# HoverBoard_CoolAndFun.net
KiCad netlist of a schematic drawn in EAGLE
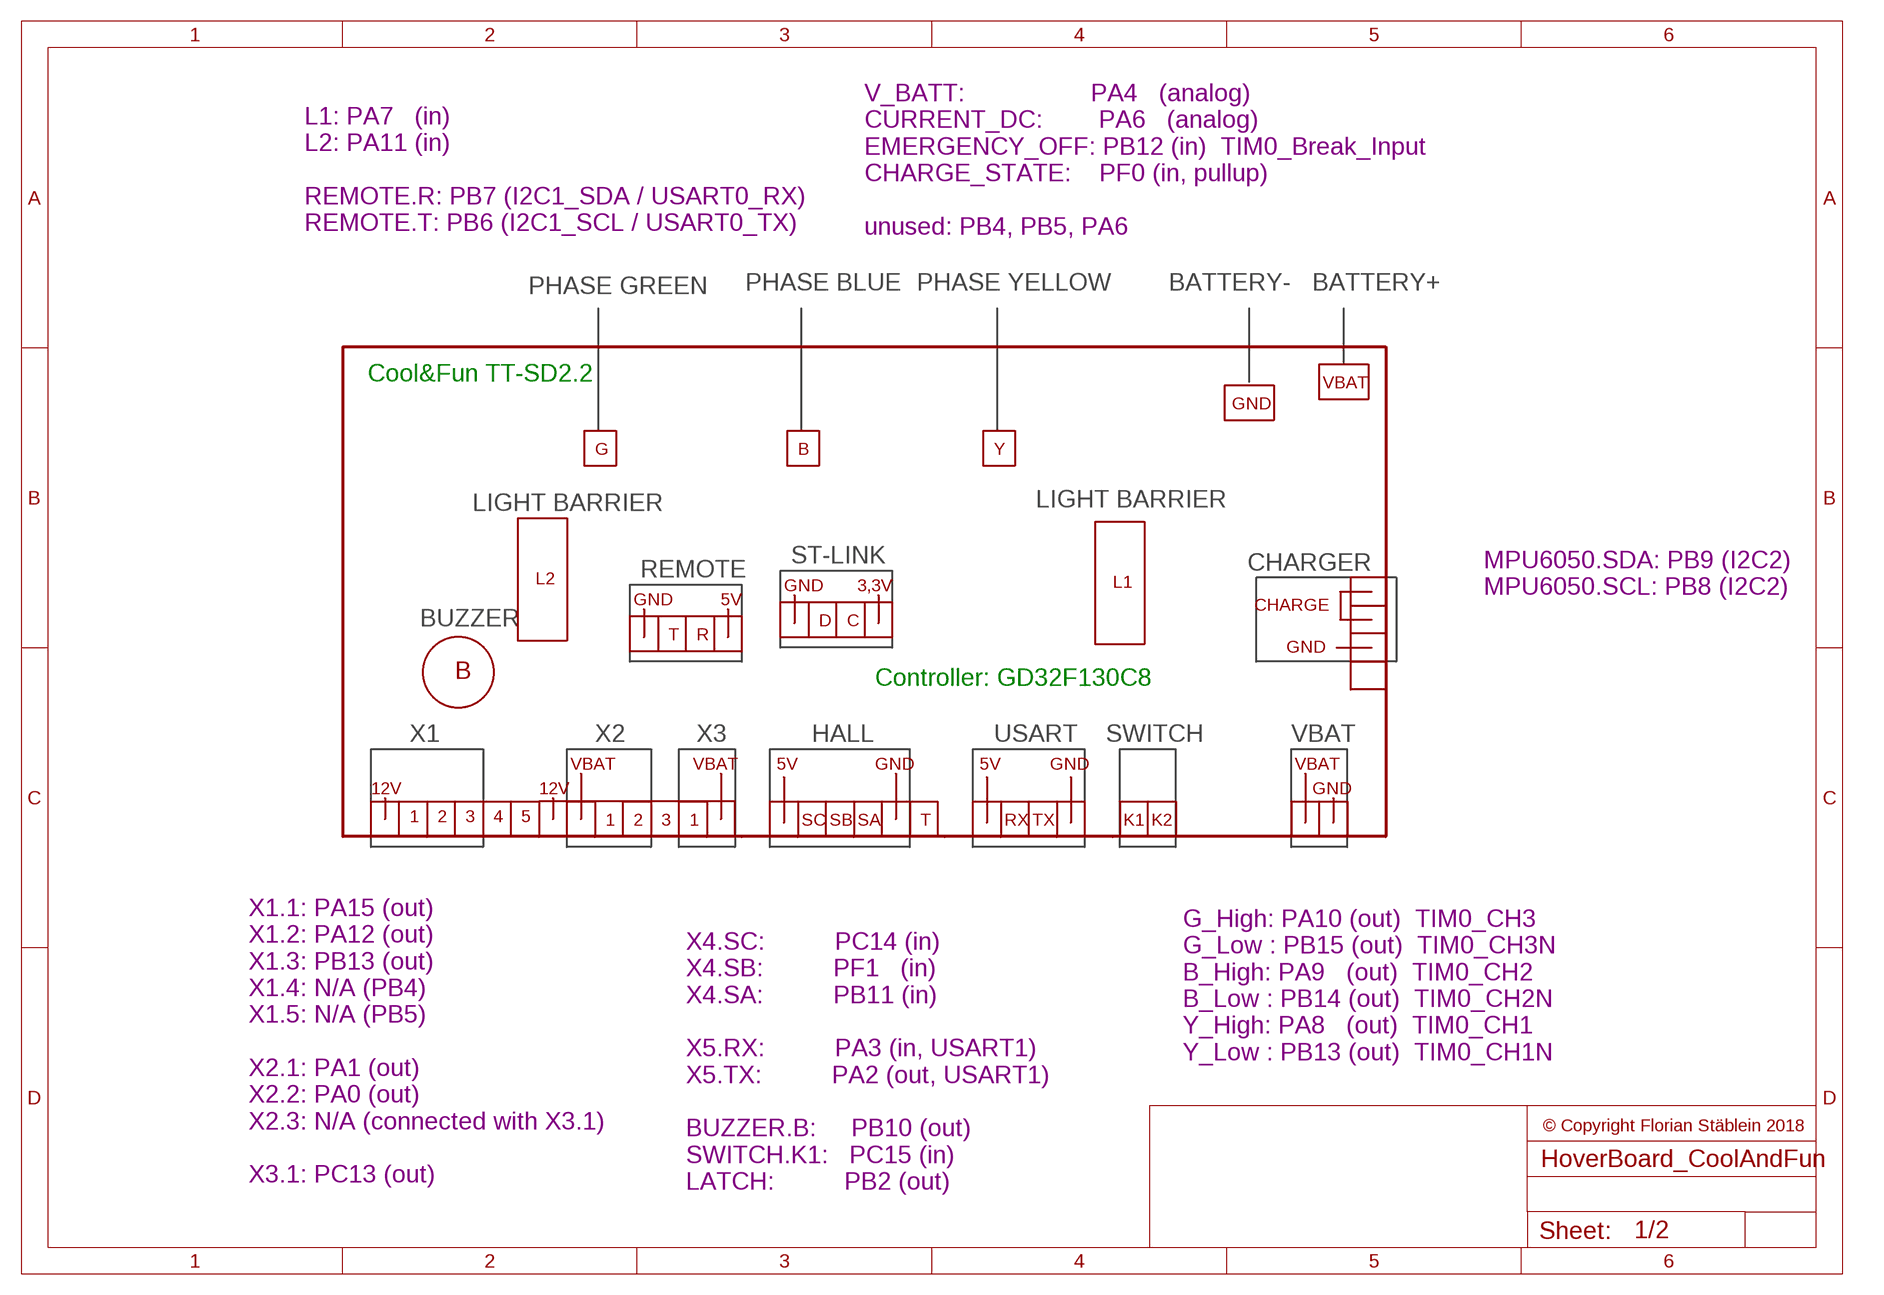
[diagram p0: schematic, sheet 1]
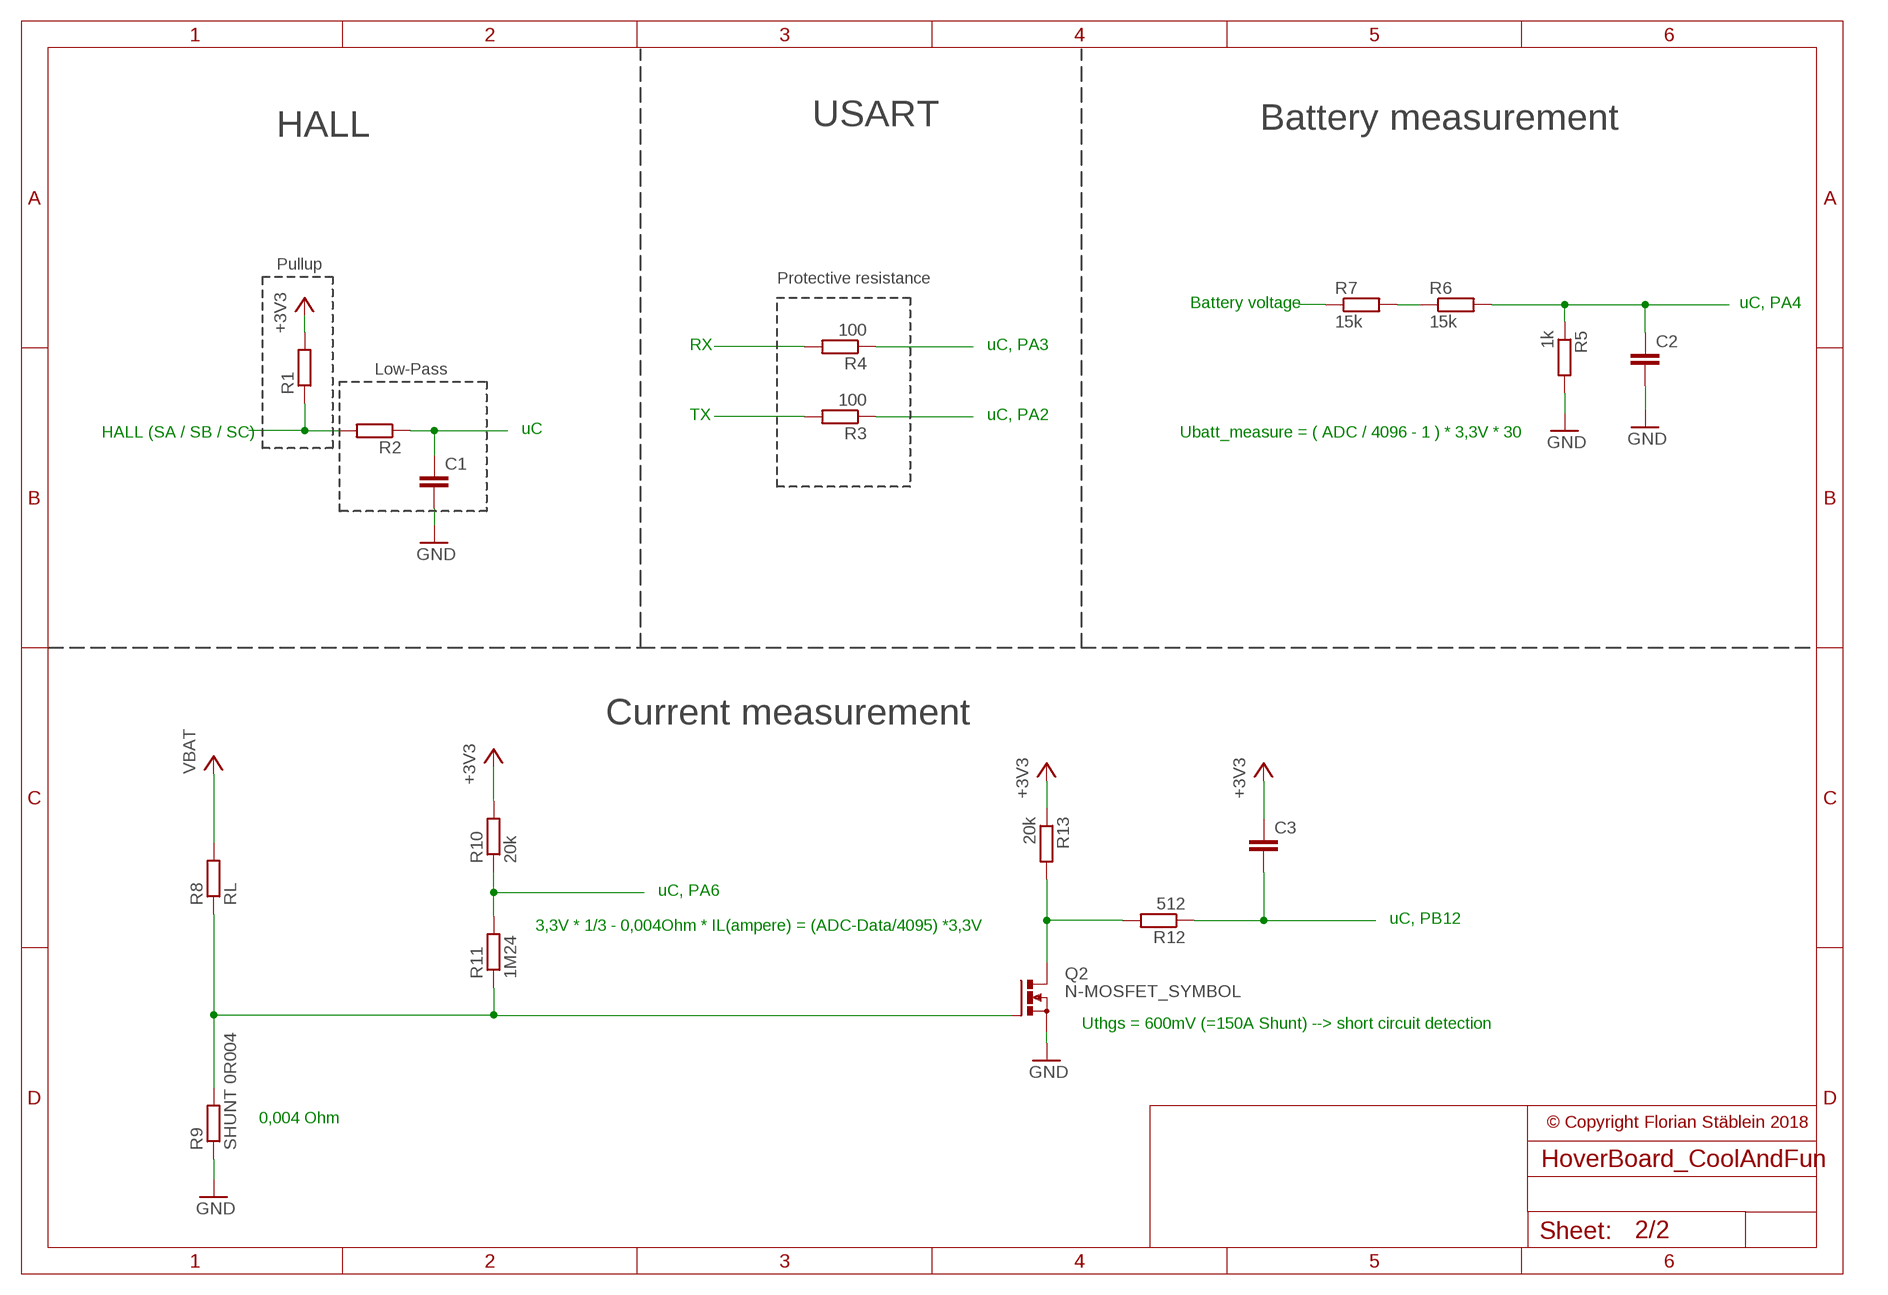
[diagram p1: schematic, sheet 2]

(export (version "E")
  (design (tool "Eeschema 10.0.6"))
  (components
    (comp (ref "C1")
      (value "C-EU025-025X050")
      (footprint "eagle-import:C025-025X050")
      (libsource (lib "eagle-import") (part "C-EU025-025X050"))
    )
    (comp (ref "C2")
      (value "C-EU025-025X050")
      (footprint "eagle-import:C025-025X050")
      (libsource (lib "eagle-import") (part "C-EU025-025X050"))
    )
    (comp (ref "C3")
      (value "C-EU025-025X050")
      (footprint "eagle-import:C025-025X050")
      (libsource (lib "eagle-import") (part "C-EU025-025X050"))
    )
    (comp (ref "R1")
      (value "R-EU_0207/2V")
      (footprint "eagle-import:0207_2V")
      (libsource (lib "eagle-import") (part "R-EU_0207/2V"))
    )
    (comp (ref "R2")
      (value "R-EU_0207/2V")
      (footprint "eagle-import:0207_2V")
      (libsource (lib "eagle-import") (part "R-EU_0207/2V"))
    )
    (comp (ref "R3")
      (value "100")
      (footprint "eagle-import:0207_2V")
      (libsource (lib "eagle-import") (part "R-EU_0207/2V"))
    )
    (comp (ref "R4")
      (value "100")
      (footprint "eagle-import:0207_2V")
      (libsource (lib "eagle-import") (part "R-EU_0207/2V"))
    )
    (comp (ref "R5")
      (value "1k")
      (footprint "eagle-import:0207_2V")
      (libsource (lib "eagle-import") (part "R-EU_0207/2V"))
    )
    (comp (ref "R6")
      (value "15k")
      (footprint "eagle-import:0207_2V")
      (libsource (lib "eagle-import") (part "R-EU_0207/2V"))
    )
    (comp (ref "R7")
      (value "15k")
      (footprint "eagle-import:0207_2V")
      (libsource (lib "eagle-import") (part "R-EU_0207/2V"))
    )
    (comp (ref "R8")
      (value "RL")
      (footprint "eagle-import:0207_2V")
      (libsource (lib "eagle-import") (part "R-EU_0207/2V"))
    )
    (comp (ref "R9")
      (value "SHUNT 0R004")
      (footprint "eagle-import:0207_2V")
      (libsource (lib "eagle-import") (part "R-EU_0207/2V"))
    )
    (comp (ref "R10")
      (value "20k")
      (footprint "eagle-import:0207_2V")
      (libsource (lib "eagle-import") (part "R-EU_0207/2V"))
    )
    (comp (ref "R11")
      (value "1M24")
      (footprint "eagle-import:0207_2V")
      (libsource (lib "eagle-import") (part "R-EU_0207/2V"))
    )
    (comp (ref "R12")
      (value "512")
      (footprint "eagle-import:0207_2V")
      (libsource (lib "eagle-import") (part "R-EU_0207/2V"))
    )
    (comp (ref "R13")
      (value "20k")
      (footprint "eagle-import:0207_2V")
      (libsource (lib "eagle-import") (part "R-EU_0207/2V"))
    )
  )
  (nets
    (net (code "1") (name "+3V3") (class "Default")
      (node (ref "C3") (pin "1") (pinfunction "1_1") (pintype "passive"))
      (node (ref "R1") (pin "2") (pinfunction "2_2") (pintype "passive"))
      (node (ref "R10") (pin "2") (pinfunction "2_2") (pintype "passive"))
      (node (ref "R13") (pin "1") (pinfunction "1_1") (pintype "passive"))
    )
    (net (code "2") (name "GND") (class "Default")
      (node (ref "C1") (pin "2") (pinfunction "2_2") (pintype "passive"))
      (node (ref "C2") (pin "2") (pinfunction "2_2") (pintype "passive"))
      (node (ref "R5") (pin "2") (pinfunction "2_2") (pintype "passive"))
      (node (ref "R9") (pin "1") (pinfunction "1_1") (pintype "passive"))
    )
    (net (code "3") (name "Net-(C1-Pad1)") (class "Default")
      (node (ref "C1") (pin "1") (pinfunction "1_1") (pintype "passive"))
      (node (ref "R2") (pin "1") (pinfunction "1_1") (pintype "passive"))
    )
    (net (code "4") (name "Net-(C2-Pad1)") (class "Default")
      (node (ref "C2") (pin "1") (pinfunction "1_1") (pintype "passive"))
      (node (ref "R5") (pin "1") (pinfunction "1_1") (pintype "passive"))
      (node (ref "R6") (pin "2") (pinfunction "2_2") (pintype "passive"))
    )
    (net (code "5") (name "Net-(C3-Pad2)") (class "Default")
      (node (ref "C3") (pin "2") (pinfunction "2_2") (pintype "passive"))
      (node (ref "R12") (pin "1") (pinfunction "1_1") (pintype "passive"))
    )
    (net (code "6") (name "Net-(R1-Pad1)") (class "Default")
      (node (ref "R1") (pin "1") (pinfunction "1_1") (pintype "passive"))
      (node (ref "R2") (pin "2") (pinfunction "2_2") (pintype "passive"))
    )
    (net (code "7") (name "Net-(R6-Pad1)") (class "Default")
      (node (ref "R6") (pin "1") (pinfunction "1_1") (pintype "passive"))
      (node (ref "R7") (pin "2") (pinfunction "2_2") (pintype "passive"))
    )
    (net (code "8") (name "Net-(R10-Pad1)") (class "Default")
      (node (ref "R10") (pin "1") (pinfunction "1_1") (pintype "passive"))
      (node (ref "R11") (pin "2") (pinfunction "2_2") (pintype "passive"))
    )
    (net (code "9") (name "Net-(R11-Pad1)") (class "Default")
      (node (ref "R11") (pin "1") (pinfunction "1_1") (pintype "passive"))
      (node (ref "R8") (pin "1") (pinfunction "1_1") (pintype "passive"))
      (node (ref "R9") (pin "2") (pinfunction "2_2") (pintype "passive"))
    )
    (net (code "10") (name "Net-(R12-Pad2)") (class "Default")
      (node (ref "R12") (pin "2") (pinfunction "2_2") (pintype "passive"))
      (node (ref "R13") (pin "2") (pinfunction "2_2") (pintype "passive"))
    )
    (net (code "11") (name "VBAT") (class "Default")
      (node (ref "R8") (pin "2") (pinfunction "2_2") (pintype "passive"))
    )
    (net (code "12") (name "unconnected-(R3-Pad1)") (class "Default")
      (node (ref "R3") (pin "1") (pinfunction "1_1") (pintype "passive"))
    )
    (net (code "13") (name "unconnected-(R3-Pad2)") (class "Default")
      (node (ref "R3") (pin "2") (pinfunction "2_2") (pintype "passive"))
    )
    (net (code "14") (name "unconnected-(R4-Pad1)") (class "Default")
      (node (ref "R4") (pin "1") (pinfunction "1_1") (pintype "passive"))
    )
    (net (code "15") (name "unconnected-(R4-Pad2)") (class "Default")
      (node (ref "R4") (pin "2") (pinfunction "2_2") (pintype "passive"))
    )
    (net (code "16") (name "unconnected-(R7-Pad1)") (class "Default")
      (node (ref "R7") (pin "1") (pinfunction "1_1") (pintype "passive"))
    )
  )
)
